# EEZ_DIB_BP3C_r2B3.net
KiCad netlist of a schematic drawn in EAGLE
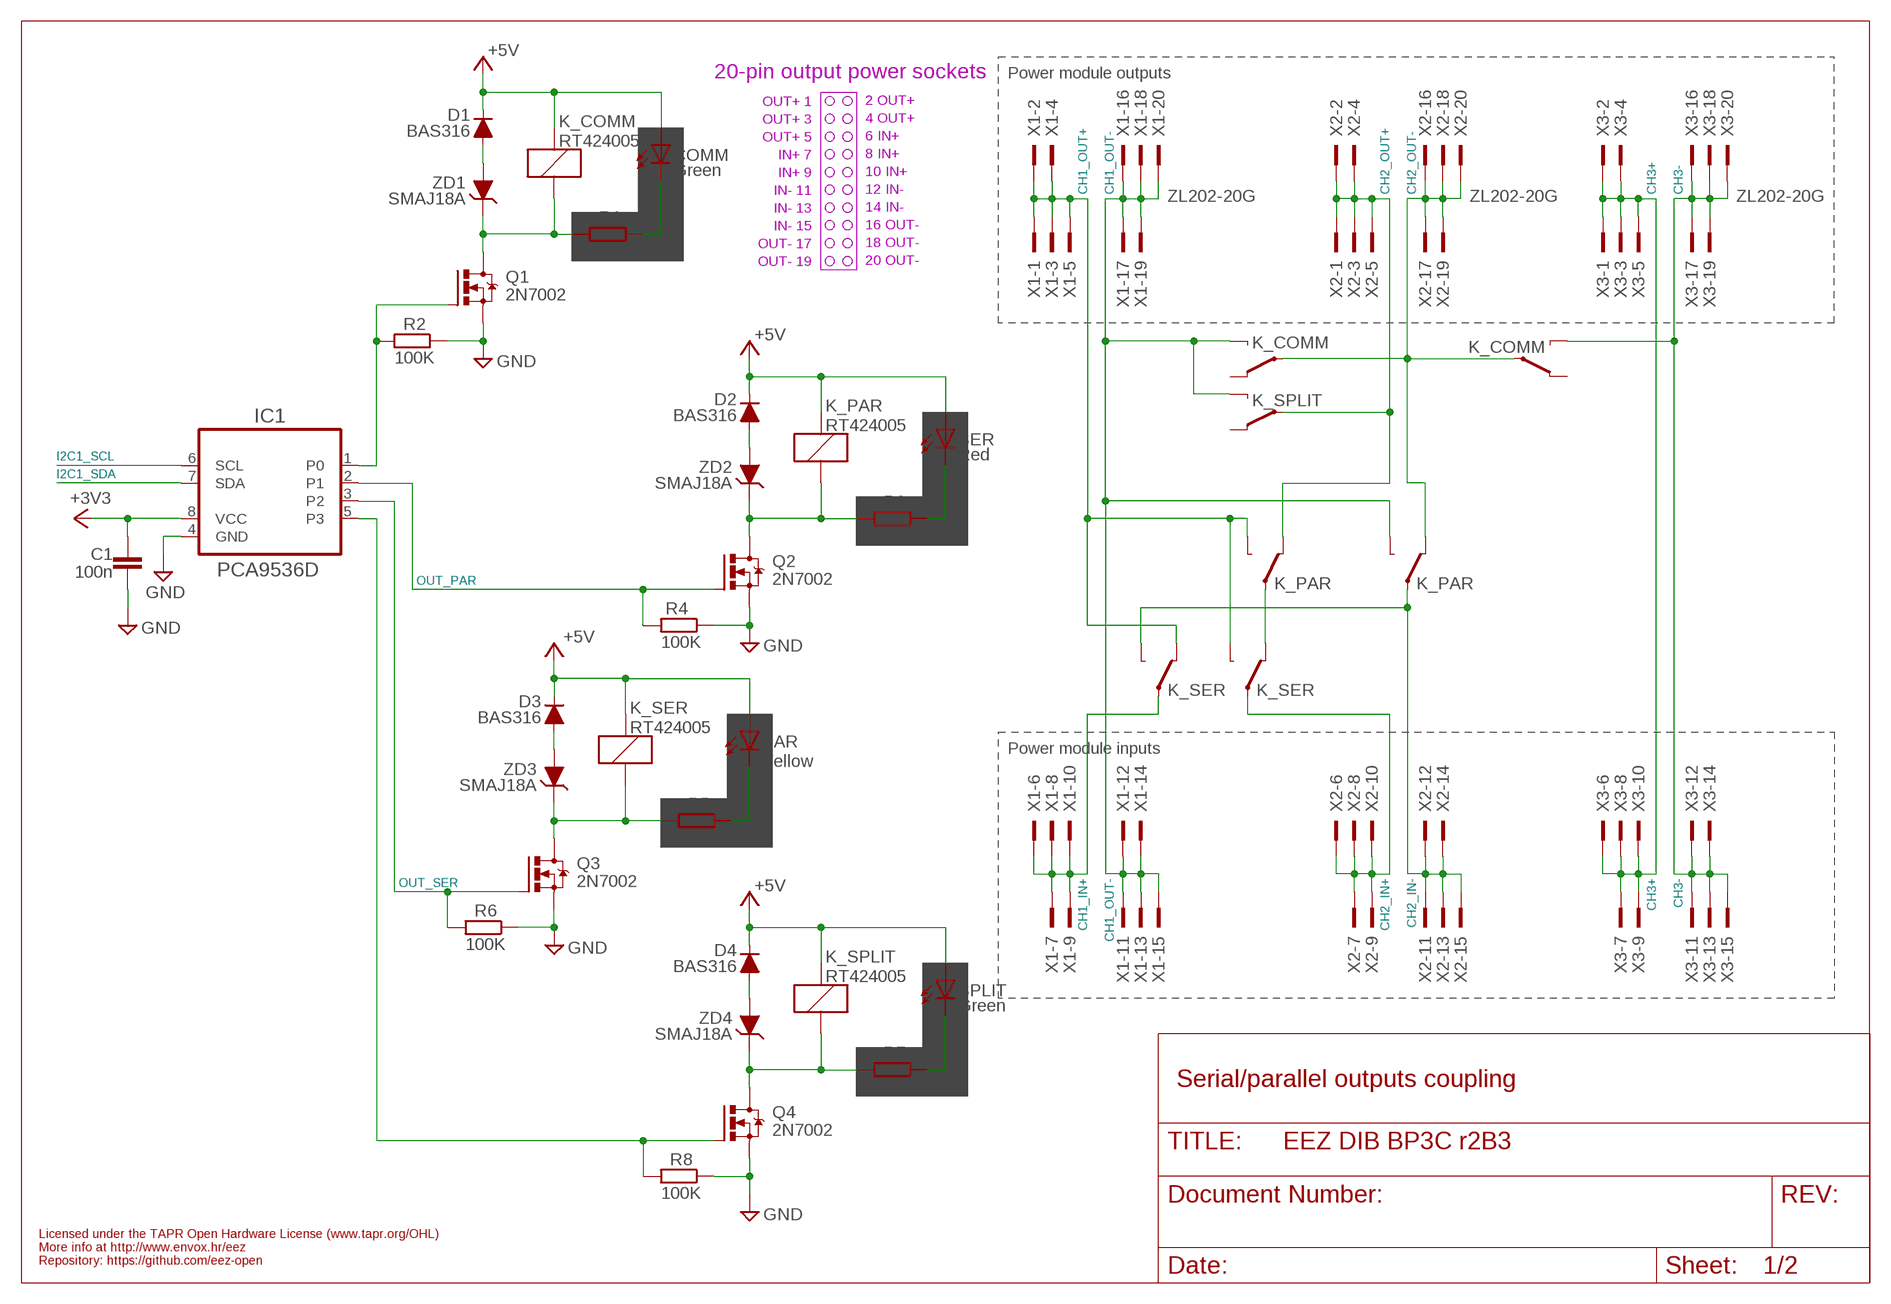
[diagram p0: schematic, sheet 1]
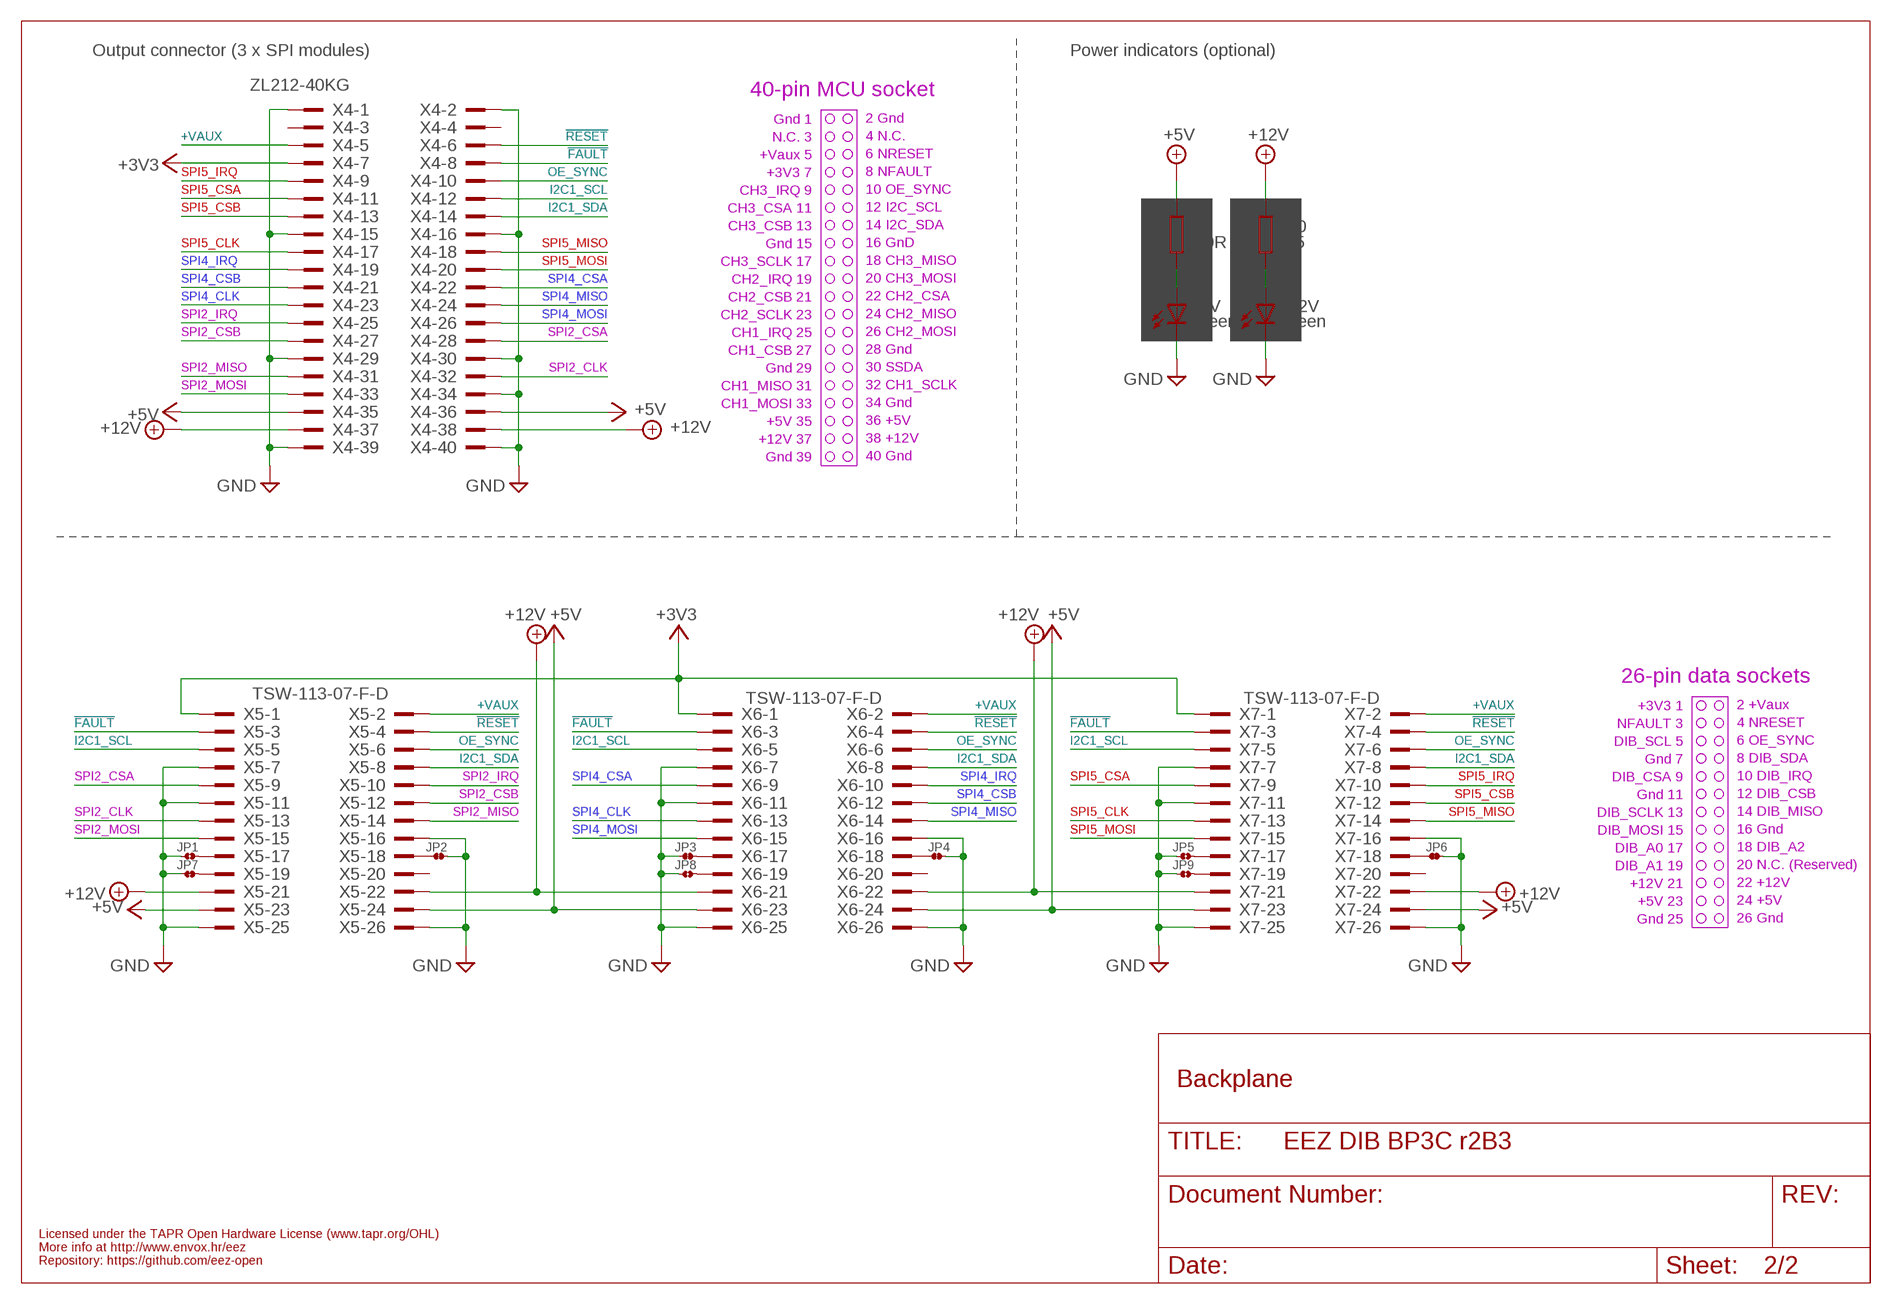
[diagram p1: schematic, sheet 2]

(export (version "E")
  (design (tool "Eeschema 10.0.6"))
  (components
    (comp (ref "+5V")
      (value "Green")
      (footprint "eagle-import:LED_0805")
      (libsource (lib "eagle-import") (part "LED0805"))
    )
    (comp (ref "+12V")
      (value "Green")
      (footprint "eagle-import:LED_0805")
      (libsource (lib "eagle-import") (part "LED0805"))
    )
    (comp (ref "JP1")
      (value "JP2-CUT")
      (footprint "eagle-import:JP2-CUT")
      (libsource (lib "eagle-import") (part "JP2-CUT"))
    )
    (comp (ref "JP2")
      (value "JP2-NOCUT")
      (footprint "eagle-import:JP2-NOCUT")
      (libsource (lib "eagle-import") (part "JP2-NOCUT"))
    )
    (comp (ref "JP3")
      (value "JP2-NOCUT")
      (footprint "eagle-import:JP2-NOCUT")
      (libsource (lib "eagle-import") (part "JP2-NOCUT"))
    )
    (comp (ref "JP4")
      (value "JP2-NOCUT")
      (footprint "eagle-import:JP2-NOCUT")
      (libsource (lib "eagle-import") (part "JP2-NOCUT"))
    )
    (comp (ref "JP5")
      (value "JP2-CUT")
      (footprint "eagle-import:JP2-CUT")
      (libsource (lib "eagle-import") (part "JP2-CUT"))
    )
    (comp (ref "JP6")
      (value "JP2-NOCUT")
      (footprint "eagle-import:JP2-NOCUT")
      (libsource (lib "eagle-import") (part "JP2-NOCUT"))
    )
    (comp (ref "JP7")
      (value "JP2-NOCUT")
      (footprint "eagle-import:JP2-NOCUT")
      (libsource (lib "eagle-import") (part "JP2-NOCUT"))
    )
    (comp (ref "JP8")
      (value "JP2-CUT")
      (footprint "eagle-import:JP2-CUT")
      (libsource (lib "eagle-import") (part "JP2-CUT"))
    )
    (comp (ref "JP9")
      (value "JP2-CUT")
      (footprint "eagle-import:JP2-CUT")
      (libsource (lib "eagle-import") (part "JP2-CUT"))
    )
    (comp (ref "R9")
      (value "470R")
      (footprint "eagle-import:R0805")
      (libsource (lib "eagle-import") (part "R-EU_R0805"))
    )
    (comp (ref "R10")
      (value "1K5")
      (footprint "eagle-import:R0805")
      (libsource (lib "eagle-import") (part "R-EU_R0805"))
    )
    (comp (ref "X4")
      (value "ZL212-40KG")
      (footprint "eagle-import:ZL212-40KG")
      (libsource (lib "eagle-import") (part "ZL212-40KG"))
    )
    (comp (ref "X5")
      (value "TSW-113-07-F-D")
      (footprint "eagle-import:TSW-113-07-F-D")
      (libsource (lib "eagle-import") (part "TSW-113-07-F-D"))
    )
    (comp (ref "X6")
      (value "TSW-113-07-F-D")
      (footprint "eagle-import:TSW-113-07-F-D")
      (libsource (lib "eagle-import") (part "TSW-113-07-F-D"))
    )
    (comp (ref "X7")
      (value "TSW-113-07-F-D")
      (footprint "eagle-import:TSW-113-07-F-D")
      (libsource (lib "eagle-import") (part "TSW-113-07-F-D"))
    )
    (comp (ref "C1")
      (value "100n")
      (footprint "eagle-import:C0603")
      (libsource (lib "eagle-import") (part "C-EUC0603"))
    )
    (comp (ref "COMM")
      (value "Green")
      (footprint "eagle-import:LED_0805")
      (libsource (lib "eagle-import") (part "LED0805"))
    )
    (comp (ref "D1")
      (value "BAS316")
      (footprint "eagle-import:SOD323-R")
      (libsource (lib "eagle-import") (part "DIODESOD323R"))
    )
    (comp (ref "D2")
      (value "BAS316")
      (footprint "eagle-import:SOD323-R")
      (libsource (lib "eagle-import") (part "DIODESOD323R"))
    )
    (comp (ref "D3")
      (value "BAS316")
      (footprint "eagle-import:SOD323-R")
      (libsource (lib "eagle-import") (part "DIODESOD323R"))
    )
    (comp (ref "D4")
      (value "BAS316")
      (footprint "eagle-import:SOD323-R")
      (libsource (lib "eagle-import") (part "DIODESOD323R"))
    )
    (comp (ref "IC1")
      (value "PCA9536D")
      (footprint "eagle-import:SOIC127P600X173-8N")
      (libsource (lib "eagle-import") (part "PCA9536D"))
    )
    (comp (ref "K_COMM")
      (value "RT424005")
      (footprint "eagle-import:RT-C_016A5_ROUND")
      (libsource (lib "eagle-import") (part "RELAY_RT314012-2"))
    )
    (comp (ref "K_PAR")
      (value "RT424005")
      (footprint "eagle-import:RT-C_016A5_ROUND")
      (libsource (lib "eagle-import") (part "RELAY_RT314012-2"))
    )
    (comp (ref "K_SER")
      (value "RT424005")
      (footprint "eagle-import:RT-C_016A5_ROUND")
      (libsource (lib "eagle-import") (part "RELAY_RT314012-2"))
    )
    (comp (ref "K_SPLIT")
      (value "RT424005")
      (footprint "eagle-import:RT-C_016A5_ROUND")
      (libsource (lib "eagle-import") (part "RELAY_RT314012-2"))
    )
    (comp (ref "PAR")
      (value "Yellow")
      (footprint "eagle-import:LED_0805")
      (libsource (lib "eagle-import") (part "LED0805"))
    )
    (comp (ref "Q1")
      (value "2N7002")
      (footprint "eagle-import:SOT103P240X110-3N")
      (fields
        (field (name "MPN") "2N7002-7-F")
        (field (name "MPN_1") "2N7002-7-F")
        (field (name "OC_FARNELL") "1713823")
        (field (name "OC_NEWARK") "25R5679")
        (field (name "PACKAGE") "SOT-23-3")
        (field (name "SUPPLIER") "DIODES INC.")
      )
      (libsource (lib "eagle-import") (part "2N7002"))
    )
    (comp (ref "Q2")
      (value "2N7002")
      (footprint "eagle-import:SOT103P240X110-3N")
      (fields
        (field (name "MPN") "2N7002-7-F")
        (field (name "MPN_1") "2N7002-7-F")
        (field (name "OC_FARNELL") "1713823")
        (field (name "OC_NEWARK") "25R5679")
        (field (name "PACKAGE") "SOT-23-3")
        (field (name "SUPPLIER") "DIODES INC.")
      )
      (libsource (lib "eagle-import") (part "2N7002"))
    )
    (comp (ref "Q3")
      (value "2N7002")
      (footprint "eagle-import:SOT103P240X110-3N")
      (fields
        (field (name "MPN") "2N7002-7-F")
        (field (name "MPN_1") "2N7002-7-F")
        (field (name "OC_FARNELL") "1713823")
        (field (name "OC_NEWARK") "25R5679")
        (field (name "PACKAGE") "SOT-23-3")
        (field (name "SUPPLIER") "DIODES INC.")
      )
      (libsource (lib "eagle-import") (part "2N7002"))
    )
    (comp (ref "Q4")
      (value "2N7002")
      (footprint "eagle-import:SOT103P240X110-3N")
      (fields
        (field (name "MPN") "2N7002-7-F")
        (field (name "MPN_1") "2N7002-7-F")
        (field (name "OC_FARNELL") "1713823")
        (field (name "OC_NEWARK") "25R5679")
        (field (name "PACKAGE") "SOT-23-3")
        (field (name "SUPPLIER") "DIODES INC.")
      )
      (libsource (lib "eagle-import") (part "2N7002"))
    )
    (comp (ref "R1")
      (value "330R")
      (footprint "eagle-import:R0805")
      (libsource (lib "eagle-import") (part "R-EU_R0805"))
    )
    (comp (ref "R2")
      (value "100K")
      (footprint "eagle-import:R0805")
      (libsource (lib "eagle-import") (part "R-EU_R0805"))
    )
    (comp (ref "R3")
      (value "330R")
      (footprint "eagle-import:R0805")
      (libsource (lib "eagle-import") (part "R-EU_R0805"))
    )
    (comp (ref "R4")
      (value "100K")
      (footprint "eagle-import:R0805")
      (libsource (lib "eagle-import") (part "R-EU_R0805"))
    )
    (comp (ref "R5")
      (value "330R")
      (footprint "eagle-import:R0805")
      (libsource (lib "eagle-import") (part "R-EU_R0805"))
    )
    (comp (ref "R6")
      (value "100K")
      (footprint "eagle-import:R0805")
      (libsource (lib "eagle-import") (part "R-EU_R0805"))
    )
    (comp (ref "R7")
      (value "330R")
      (footprint "eagle-import:R0805")
      (libsource (lib "eagle-import") (part "R-EU_R0805"))
    )
    (comp (ref "R8")
      (value "100K")
      (footprint "eagle-import:R0805")
      (libsource (lib "eagle-import") (part "R-EU_R0805"))
    )
    (comp (ref "SER")
      (value "Red")
      (footprint "eagle-import:LED_0805")
      (libsource (lib "eagle-import") (part "LED0805"))
    )
    (comp (ref "SPLIT")
      (value "Green")
      (footprint "eagle-import:LED_0805")
      (libsource (lib "eagle-import") (part "LED0805"))
    )
    (comp (ref "X1")
      (value "ZL202-20G")
      (footprint "eagle-import:DS1021-2_10SF11")
      (libsource (lib "eagle-import") (part "DS1021-210SF11"))
    )
    (comp (ref "X2")
      (value "ZL202-20G")
      (footprint "eagle-import:DS1021-2_10SF11")
      (libsource (lib "eagle-import") (part "DS1021-210SF11"))
    )
    (comp (ref "X3")
      (value "ZL202-20G")
      (footprint "eagle-import:DS1021-2_10SF11")
      (libsource (lib "eagle-import") (part "DS1021-210SF11"))
    )
    (comp (ref "ZD1")
      (value "SMAJ18A")
      (footprint "eagle-import:DO214AC")
      (libsource (lib "eagle-import") (part "PSMAXX"))
    )
    (comp (ref "ZD2")
      (value "SMAJ18A")
      (footprint "eagle-import:DO214AC")
      (libsource (lib "eagle-import") (part "PSMAXX"))
    )
    (comp (ref "ZD3")
      (value "SMAJ18A")
      (footprint "eagle-import:DO214AC")
      (libsource (lib "eagle-import") (part "PSMAXX"))
    )
    (comp (ref "ZD4")
      (value "SMAJ18A")
      (footprint "eagle-import:DO214AC")
      (libsource (lib "eagle-import") (part "PSMAXX"))
    )
  )
  (nets
    (net (code "1") (name "+3V3") (class "Default")
      (node (ref "C1") (pin "1") (pinfunction "1_1") (pintype "passive"))
      (node (ref "IC1") (pin "8") (pinfunction "VCC_8") (pintype "passive"))
      (node (ref "X4") (pin "7") (pinfunction "1_7") (pintype "passive"))
      (node (ref "X5") (pin "1") (pinfunction "1_1") (pintype "passive"))
      (node (ref "X6") (pin "1") (pinfunction "1_1") (pintype "passive"))
      (node (ref "X7") (pin "1") (pinfunction "1_1") (pintype "passive"))
    )
    (net (code "2") (name "+5V") (class "Default")
      (node (ref "COMM") (pin "A") (pinfunction "A_A") (pintype "passive"))
      (node (ref "D1") (pin "C") (pinfunction "C_C") (pintype "passive"))
      (node (ref "D2") (pin "C") (pinfunction "C_C") (pintype "passive"))
      (node (ref "D3") (pin "C") (pinfunction "C_C") (pintype "passive"))
      (node (ref "D4") (pin "C") (pinfunction "C_C") (pintype "passive"))
      (node (ref "K_COMM") (pin "A2") (pinfunction "C1_A2") (pintype "passive"))
      (node (ref "K_PAR") (pin "A2") (pinfunction "C1_A2") (pintype "passive"))
      (node (ref "K_SER") (pin "A2") (pinfunction "C1_A2") (pintype "passive"))
      (node (ref "K_SPLIT") (pin "A2") (pinfunction "C1_A2") (pintype "passive"))
      (node (ref "PAR") (pin "A") (pinfunction "A_A") (pintype "passive"))
      (node (ref "R9") (pin "1") (pinfunction "1_1") (pintype "passive"))
      (node (ref "SER") (pin "A") (pinfunction "A_A") (pintype "passive"))
      (node (ref "SPLIT") (pin "A") (pinfunction "A_A") (pintype "passive"))
      (node (ref "X4") (pin "35") (pinfunction "1_35") (pintype "passive"))
      (node (ref "X4") (pin "36") (pinfunction "1_36") (pintype "passive"))
      (node (ref "X5") (pin "23") (pinfunction "1_23") (pintype "passive"))
      (node (ref "X5") (pin "24") (pinfunction "1_24") (pintype "passive"))
      (node (ref "X6") (pin "23") (pinfunction "1_23") (pintype "passive"))
      (node (ref "X6") (pin "24") (pinfunction "1_24") (pintype "passive"))
      (node (ref "X7") (pin "23") (pinfunction "1_23") (pintype "passive"))
      (node (ref "X7") (pin "24") (pinfunction "1_24") (pintype "passive"))
    )
    (net (code "3") (name "+12V") (class "Default")
      (node (ref "R10") (pin "1") (pinfunction "1_1") (pintype "passive"))
      (node (ref "X4") (pin "37") (pinfunction "1_37") (pintype "passive"))
      (node (ref "X4") (pin "38") (pinfunction "1_38") (pintype "passive"))
      (node (ref "X5") (pin "21") (pinfunction "1_21") (pintype "passive"))
      (node (ref "X5") (pin "22") (pinfunction "1_22") (pintype "passive"))
      (node (ref "X6") (pin "21") (pinfunction "1_21") (pintype "passive"))
      (node (ref "X6") (pin "22") (pinfunction "1_22") (pintype "passive"))
      (node (ref "X7") (pin "21") (pinfunction "1_21") (pintype "passive"))
      (node (ref "X7") (pin "22") (pinfunction "1_22") (pintype "passive"))
    )
    (net (code "4") (name "+VAUX") (class "Default")
      (node (ref "X4") (pin "5") (pinfunction "1_5") (pintype "passive"))
      (node (ref "X5") (pin "2") (pinfunction "1_2") (pintype "passive"))
      (node (ref "X6") (pin "2") (pinfunction "1_2") (pintype "passive"))
      (node (ref "X7") (pin "2") (pinfunction "1_2") (pintype "passive"))
    )
    (net (code "5") (name "CH1_IN+") (class "Default")
      (node (ref "K_SER") (pin "11A") (pinfunction "P_11A") (pintype "passive"))
      (node (ref "X1") (pin "10") (pinfunction "1_10") (pintype "passive"))
      (node (ref "X1") (pin "6") (pinfunction "1_6") (pintype "passive"))
      (node (ref "X1") (pin "7") (pinfunction "1_7") (pintype "passive"))
      (node (ref "X1") (pin "8") (pinfunction "1_8") (pintype "passive"))
      (node (ref "X1") (pin "9") (pinfunction "1_9") (pintype "passive"))
    )
    (net (code "6") (name "CH1_OUT+") (class "Default")
      (node (ref "K_PAR") (pin "14A") (pinfunction "O_14A") (pintype "passive"))
      (node (ref "K_SER") (pin "12A") (pinfunction "S_12A") (pintype "passive"))
      (node (ref "K_SER") (pin "14B") (pinfunction "O_14B") (pintype "passive"))
      (node (ref "X1") (pin "1") (pinfunction "1_1") (pintype "passive"))
      (node (ref "X1") (pin "2") (pinfunction "1_2") (pintype "passive"))
      (node (ref "X1") (pin "3") (pinfunction "1_3") (pintype "passive"))
      (node (ref "X1") (pin "4") (pinfunction "1_4") (pintype "passive"))
      (node (ref "X1") (pin "5") (pinfunction "1_5") (pintype "passive"))
    )
    (net (code "7") (name "CH1_OUT-") (class "Default")
      (node (ref "K_COMM") (pin "14A") (pinfunction "O_14A") (pintype "passive"))
      (node (ref "K_PAR") (pin "14B") (pinfunction "O_14B") (pintype "passive"))
      (node (ref "K_SPLIT") (pin "14A") (pinfunction "O_14A") (pintype "passive"))
      (node (ref "X1") (pin "11") (pinfunction "1_11") (pintype "passive"))
      (node (ref "X1") (pin "12") (pinfunction "1_12") (pintype "passive"))
      (node (ref "X1") (pin "13") (pinfunction "1_13") (pintype "passive"))
      (node (ref "X1") (pin "14") (pinfunction "1_14") (pintype "passive"))
      (node (ref "X1") (pin "15") (pinfunction "1_15") (pintype "passive"))
      (node (ref "X1") (pin "16") (pinfunction "1_16") (pintype "passive"))
      (node (ref "X1") (pin "17") (pinfunction "1_17") (pintype "passive"))
      (node (ref "X1") (pin "18") (pinfunction "1_18") (pintype "passive"))
      (node (ref "X1") (pin "19") (pinfunction "1_19") (pintype "passive"))
      (node (ref "X1") (pin "20") (pinfunction "1_20") (pintype "passive"))
    )
    (net (code "8") (name "CH2_IN+") (class "Default")
      (node (ref "K_SER") (pin "11B") (pinfunction "P_11B") (pintype "passive"))
      (node (ref "X2") (pin "10") (pinfunction "1_10") (pintype "passive"))
      (node (ref "X2") (pin "6") (pinfunction "1_6") (pintype "passive"))
      (node (ref "X2") (pin "7") (pinfunction "1_7") (pintype "passive"))
      (node (ref "X2") (pin "8") (pinfunction "1_8") (pintype "passive"))
      (node (ref "X2") (pin "9") (pinfunction "1_9") (pintype "passive"))
    )
    (net (code "9") (name "CH2_IN-") (class "Default")
      (node (ref "K_PAR") (pin "11B") (pinfunction "P_11B") (pintype "passive"))
      (node (ref "K_SER") (pin "14A") (pinfunction "O_14A") (pintype "passive"))
      (node (ref "X2") (pin "11") (pinfunction "1_11") (pintype "passive"))
      (node (ref "X2") (pin "12") (pinfunction "1_12") (pintype "passive"))
      (node (ref "X2") (pin "13") (pinfunction "1_13") (pintype "passive"))
      (node (ref "X2") (pin "14") (pinfunction "1_14") (pintype "passive"))
      (node (ref "X2") (pin "15") (pinfunction "1_15") (pintype "passive"))
    )
    (net (code "10") (name "CH2_OUT+") (class "Default")
      (node (ref "K_PAR") (pin "12A") (pinfunction "S_12A") (pintype "passive"))
      (node (ref "K_SPLIT") (pin "11A") (pinfunction "P_11A") (pintype "passive"))
      (node (ref "X2") (pin "1") (pinfunction "1_1") (pintype "passive"))
      (node (ref "X2") (pin "2") (pinfunction "1_2") (pintype "passive"))
      (node (ref "X2") (pin "3") (pinfunction "1_3") (pintype "passive"))
      (node (ref "X2") (pin "4") (pinfunction "1_4") (pintype "passive"))
      (node (ref "X2") (pin "5") (pinfunction "1_5") (pintype "passive"))
    )
    (net (code "11") (name "CH2_OUT-") (class "Default")
      (node (ref "K_COMM") (pin "11A") (pinfunction "P_11A") (pintype "passive"))
      (node (ref "K_COMM") (pin "11B") (pinfunction "P_11B") (pintype "passive"))
      (node (ref "K_PAR") (pin "12B") (pinfunction "S_12B") (pintype "passive"))
      (node (ref "X2") (pin "16") (pinfunction "1_16") (pintype "passive"))
      (node (ref "X2") (pin "17") (pinfunction "1_17") (pintype "passive"))
      (node (ref "X2") (pin "18") (pinfunction "1_18") (pintype "passive"))
      (node (ref "X2") (pin "19") (pinfunction "1_19") (pintype "passive"))
      (node (ref "X2") (pin "20") (pinfunction "1_20") (pintype "passive"))
    )
    (net (code "12") (name "CH3+") (class "Default")
      (node (ref "X3") (pin "1") (pinfunction "1_1") (pintype "passive"))
      (node (ref "X3") (pin "10") (pinfunction "1_10") (pintype "passive"))
      (node (ref "X3") (pin "2") (pinfunction "1_2") (pintype "passive"))
      (node (ref "X3") (pin "3") (pinfunction "1_3") (pintype "passive"))
      (node (ref "X3") (pin "4") (pinfunction "1_4") (pintype "passive"))
      (node (ref "X3") (pin "5") (pinfunction "1_5") (pintype "passive"))
      (node (ref "X3") (pin "6") (pinfunction "1_6") (pintype "passive"))
      (node (ref "X3") (pin "7") (pinfunction "1_7") (pintype "passive"))
      (node (ref "X3") (pin "8") (pinfunction "1_8") (pintype "passive"))
      (node (ref "X3") (pin "9") (pinfunction "1_9") (pintype "passive"))
    )
    (net (code "13") (name "CH3-") (class "Default")
      (node (ref "K_COMM") (pin "14B") (pinfunction "O_14B") (pintype "passive"))
      (node (ref "X3") (pin "11") (pinfunction "1_11") (pintype "passive"))
      (node (ref "X3") (pin "12") (pinfunction "1_12") (pintype "passive"))
      (node (ref "X3") (pin "13") (pinfunction "1_13") (pintype "passive"))
      (node (ref "X3") (pin "14") (pinfunction "1_14") (pintype "passive"))
      (node (ref "X3") (pin "15") (pinfunction "1_15") (pintype "passive"))
      (node (ref "X3") (pin "16") (pinfunction "1_16") (pintype "passive"))
      (node (ref "X3") (pin "17") (pinfunction "1_17") (pintype "passive"))
      (node (ref "X3") (pin "18") (pinfunction "1_18") (pintype "passive"))
      (node (ref "X3") (pin "19") (pinfunction "1_19") (pintype "passive"))
      (node (ref "X3") (pin "20") (pinfunction "1_20") (pintype "passive"))
    )
    (net (code "14") (name "GND") (class "Default")
      (node (ref "+12V") (pin "C") (pinfunction "C_C") (pintype "passive"))
      (node (ref "+5V") (pin "C") (pinfunction "C_C") (pintype "passive"))
      (node (ref "C1") (pin "2") (pinfunction "2_2") (pintype "passive"))
      (node (ref "IC1") (pin "4") (pinfunction "GND_4") (pintype "passive"))
      (node (ref "JP1") (pin "1") (pinfunction "1_1") (pintype "passive"))
      (node (ref "JP2") (pin "2") (pinfunction "2_2") (pintype "passive"))
      (node (ref "JP3") (pin "1") (pinfunction "1_1") (pintype "passive"))
      (node (ref "JP4") (pin "2") (pinfunction "2_2") (pintype "passive"))
      (node (ref "JP5") (pin "1") (pinfunction "1_1") (pintype "passive"))
      (node (ref "JP6") (pin "2") (pinfunction "2_2") (pintype "passive"))
      (node (ref "JP7") (pin "1") (pinfunction "1_1") (pintype "passive"))
      (node (ref "JP8") (pin "1") (pinfunction "1_1") (pintype "passive"))
      (node (ref "JP9") (pin "1") (pinfunction "1_1") (pintype "passive"))
      (node (ref "Q1") (pin "2") (pinfunction "S_2") (pintype "passive"))
      (node (ref "Q2") (pin "2") (pinfunction "S_2") (pintype "passive"))
      (node (ref "Q3") (pin "2") (pinfunction "S_2") (pintype "passive"))
      (node (ref "Q4") (pin "2") (pinfunction "S_2") (pintype "passive"))
      (node (ref "R2") (pin "1") (pinfunction "1_1") (pintype "passive"))
      (node (ref "R4") (pin "1") (pinfunction "1_1") (pintype "passive"))
      (node (ref "R6") (pin "1") (pinfunction "1_1") (pintype "passive"))
      (node (ref "R8") (pin "1") (pinfunction "1_1") (pintype "passive"))
      (node (ref "X4") (pin "1") (pinfunction "1_1") (pintype "passive"))
      (node (ref "X4") (pin "15") (pinfunction "1_15") (pintype "passive"))
      (node (ref "X4") (pin "16") (pinfunction "1_16") (pintype "passive"))
      (node (ref "X4") (pin "2") (pinfunction "1_2") (pintype "passive"))
      (node (ref "X4") (pin "29") (pinfunction "1_29") (pintype "passive"))
      (node (ref "X4") (pin "30") (pinfunction "1_30") (pintype "passive"))
      (node (ref "X4") (pin "34") (pinfunction "1_34") (pintype "passive"))
      (node (ref "X4") (pin "39") (pinfunction "1_39") (pintype "passive"))
      (node (ref "X4") (pin "40") (pinfunction "1_40") (pintype "passive"))
      (node (ref "X5") (pin "11") (pinfunction "1_11") (pintype "passive"))
      (node (ref "X5") (pin "16") (pinfunction "1_16") (pintype "passive"))
      (node (ref "X5") (pin "25") (pinfunction "1_25") (pintype "passive"))
      (node (ref "X5") (pin "26") (pinfunction "1_26") (pintype "passive"))
      (node (ref "X5") (pin "7") (pinfunction "1_7") (pintype "passive"))
      (node (ref "X6") (pin "11") (pinfunction "1_11") (pintype "passive"))
      (node (ref "X6") (pin "16") (pinfunction "1_16") (pintype "passive"))
      (node (ref "X6") (pin "25") (pinfunction "1_25") (pintype "passive"))
      (node (ref "X6") (pin "26") (pinfunction "1_26") (pintype "passive"))
      (node (ref "X6") (pin "7") (pinfunction "1_7") (pintype "passive"))
      (node (ref "X7") (pin "11") (pinfunction "1_11") (pintype "passive"))
      (node (ref "X7") (pin "16") (pinfunction "1_16") (pintype "passive"))
      (node (ref "X7") (pin "25") (pinfunction "1_25") (pintype "passive"))
      (node (ref "X7") (pin "26") (pinfunction "1_26") (pintype "passive"))
      (node (ref "X7") (pin "7") (pinfunction "1_7") (pintype "passive"))
    )
    (net (code "15") (name "I2C1_SCL") (class "Default")
      (node (ref "IC1") (pin "6") (pinfunction "SCL_6") (pintype "input"))
      (node (ref "X4") (pin "12") (pinfunction "1_12") (pintype "passive"))
      (node (ref "X5") (pin "5") (pinfunction "1_5") (pintype "passive"))
      (node (ref "X6") (pin "5") (pinfunction "1_5") (pintype "passive"))
      (node (ref "X7") (pin "5") (pinfunction "1_5") (pintype "passive"))
    )
    (net (code "16") (name "I2C1_SDA") (class "Default")
      (node (ref "IC1") (pin "7") (pinfunction "SDA_7") (pintype "bidirectional"))
      (node (ref "X4") (pin "14") (pinfunction "1_14") (pintype "passive"))
      (node (ref "X5") (pin "8") (pinfunction "1_8") (pintype "passive"))
      (node (ref "X6") (pin "8") (pinfunction "1_8") (pintype "passive"))
      (node (ref "X7") (pin "8") (pinfunction "1_8") (pintype "passive"))
    )
    (net (code "17") (name "Net-(+5V-PadA)") (class "Default")
      (node (ref "+5V") (pin "A") (pinfunction "A_A") (pintype "passive"))
      (node (ref "R9") (pin "2") (pinfunction "2_2") (pintype "passive"))
    )
    (net (code "18") (name "Net-(+12V-PadA)") (class "Default")
      (node (ref "+12V") (pin "A") (pinfunction "A_A") (pintype "passive"))
      (node (ref "R10") (pin "2") (pinfunction "2_2") (pintype "passive"))
    )
    (net (code "19") (name "Net-(COMM-PadC)") (class "Default")
      (node (ref "COMM") (pin "C") (pinfunction "C_C") (pintype "passive"))
      (node (ref "R1") (pin "1") (pinfunction "1_1") (pintype "passive"))
    )
    (net (code "20") (name "Net-(D1-PadA)") (class "Default")
      (node (ref "D1") (pin "A") (pinfunction "A_A") (pintype "passive"))
      (node (ref "ZD1") (pin "A") (pinfunction "A_A") (pintype "passive"))
    )
    (net (code "21") (name "Net-(D2-PadA)") (class "Default")
      (node (ref "D2") (pin "A") (pinfunction "A_A") (pintype "passive"))
      (node (ref "ZD2") (pin "A") (pinfunction "A_A") (pintype "passive"))
    )
    (net (code "22") (name "Net-(D3-PadA)") (class "Default")
      (node (ref "D3") (pin "A") (pinfunction "A_A") (pintype "passive"))
      (node (ref "ZD3") (pin "A") (pinfunction "A_A") (pintype "passive"))
    )
    (net (code "23") (name "Net-(D4-PadA)") (class "Default")
      (node (ref "D4") (pin "A") (pinfunction "A_A") (pintype "passive"))
      (node (ref "ZD4") (pin "A") (pinfunction "A_A") (pintype "passive"))
    )
    (net (code "24") (name "Net-(IC1-P0)") (class "Default")
      (node (ref "IC1") (pin "1") (pinfunction "P0_1") (pintype "bidirectional"))
      (node (ref "Q1") (pin "1") (pinfunction "G_1") (pintype "passive"))
      (node (ref "R2") (pin "2") (pinfunction "2_2") (pintype "passive"))
    )
    (net (code "25") (name "Net-(IC1-P3)") (class "Default")
      (node (ref "IC1") (pin "5") (pinfunction "P3_5") (pintype "bidirectional"))
      (node (ref "Q4") (pin "1") (pinfunction "G_1") (pintype "passive"))
      (node (ref "R8") (pin "2") (pinfunction "2_2") (pintype "passive"))
    )
    (net (code "26") (name "Net-(K_COMMC-C2)") (class "Default")
      (node (ref "K_COMM") (pin "A1") (pinfunction "C2_A1") (pintype "passive"))
      (node (ref "Q1") (pin "3") (pinfunction "D_3") (pintype "passive"))
      (node (ref "R1") (pin "2") (pinfunction "2_2") (pintype "passive"))
      (node (ref "ZD1") (pin "C") (pinfunction "C_C") (pintype "passive"))
    )
    (net (code "27") (name "Net-(K_PARA-P)") (class "Default")
      (node (ref "K_PAR") (pin "11A") (pinfunction "P_11A") (pintype "passive"))
      (node (ref "K_SER") (pin "12B") (pinfunction "S_12B") (pintype "passive"))
    )
    (net (code "28") (name "Net-(K_PARC-C2)") (class "Default")
      (node (ref "K_PAR") (pin "A1") (pinfunction "C2_A1") (pintype "passive"))
      (node (ref "Q2") (pin "3") (pinfunction "D_3") (pintype "passive"))
      (node (ref "R3") (pin "2") (pinfunction "2_2") (pintype "passive"))
      (node (ref "ZD2") (pin "C") (pinfunction "C_C") (pintype "passive"))
    )
    (net (code "29") (name "Net-(K_SERC-C2)") (class "Default")
      (node (ref "K_SER") (pin "A1") (pinfunction "C2_A1") (pintype "passive"))
      (node (ref "Q3") (pin "3") (pinfunction "D_3") (pintype "passive"))
      (node (ref "R5") (pin "2") (pinfunction "2_2") (pintype "passive"))
      (node (ref "ZD3") (pin "C") (pinfunction "C_C") (pintype "passive"))
    )
    (net (code "30") (name "Net-(K_SPLITC-C2)") (class "Default")
      (node (ref "K_SPLIT") (pin "A1") (pinfunction "C2_A1") (pintype "passive"))
      (node (ref "Q4") (pin "3") (pinfunction "D_3") (pintype "passive"))
      (node (ref "R7") (pin "2") (pinfunction "2_2") (pintype "passive"))
      (node (ref "ZD4") (pin "C") (pinfunction "C_C") (pintype "passive"))
    )
    (net (code "31") (name "Net-(PAR-PadC)") (class "Default")
      (node (ref "PAR") (pin "C") (pinfunction "C_C") (pintype "passive"))
      (node (ref "R5") (pin "1") (pinfunction "1_1") (pintype "passive"))
    )
    (net (code "32") (name "Net-(R3-Pad1)") (class "Default")
      (node (ref "R3") (pin "1") (pinfunction "1_1") (pintype "passive"))
      (node (ref "SER") (pin "C") (pinfunction "C_C") (pintype "passive"))
    )
    (net (code "33") (name "Net-(R7-Pad1)") (class "Default")
      (node (ref "R7") (pin "1") (pinfunction "1_1") (pintype "passive"))
      (node (ref "SPLIT") (pin "C") (pinfunction "C_C") (pintype "passive"))
    )
    (net (code "34") (name "Net-(X5I-1)") (class "Default")
      (node (ref "JP1") (pin "2") (pinfunction "2_2") (pintype "passive"))
      (node (ref "X5") (pin "17") (pinfunction "1_17") (pintype "passive"))
    )
    (net (code "35") (name "Net-(X5J-1)") (class "Default")
      (node (ref "JP2") (pin "1") (pinfunction "1_1") (pintype "passive"))
      (node (ref "X5") (pin "18") (pinfunction "1_18") (pintype "passive"))
    )
    (net (code "36") (name "Net-(X5K-1)") (class "Default")
      (node (ref "JP7") (pin "2") (pinfunction "2_2") (pintype "passive"))
      (node (ref "X5") (pin "19") (pinfunction "1_19") (pintype "passive"))
    )
    (net (code "37") (name "Net-(X6I-1)") (class "Default")
      (node (ref "JP3") (pin "2") (pinfunction "2_2") (pintype "passive"))
      (node (ref "X6") (pin "17") (pinfunction "1_17") (pintype "passive"))
    )
    (net (code "38") (name "Net-(X6J-1)") (class "Default")
      (node (ref "JP4") (pin "1") (pinfunction "1_1") (pintype "passive"))
      (node (ref "X6") (pin "18") (pinfunction "1_18") (pintype "passive"))
    )
    (net (code "39") (name "Net-(X6K-1)") (class "Default")
      (node (ref "JP8") (pin "2") (pinfunction "2_2") (pintype "passive"))
      (node (ref "X6") (pin "19") (pinfunction "1_19") (pintype "passive"))
    )
    (net (code "40") (name "Net-(X7I-1)") (class "Default")
      (node (ref "JP5") (pin "2") (pinfunction "2_2") (pintype "passive"))
      (node (ref "X7") (pin "17") (pinfunction "1_17") (pintype "passive"))
    )
    (net (code "41") (name "Net-(X7J-1)") (class "Default")
      (node (ref "JP6") (pin "1") (pinfunction "1_1") (pintype "passive"))
      (node (ref "X7") (pin "18") (pinfunction "1_18") (pintype "passive"))
    )
    (net (code "42") (name "Net-(X7K-1)") (class "Default")
      (node (ref "JP9") (pin "2") (pinfunction "2_2") (pintype "passive"))
      (node (ref "X7") (pin "19") (pinfunction "1_19") (pintype "passive"))
    )
    (net (code "43") (name "OE_SYNC") (class "Default")
      (node (ref "X4") (pin "10") (pinfunction "1_10") (pintype "passive"))
      (node (ref "X5") (pin "6") (pinfunction "1_6") (pintype "passive"))
      (node (ref "X6") (pin "6") (pinfunction "1_6") (pintype "passive"))
      (node (ref "X7") (pin "6") (pinfunction "1_6") (pintype "passive"))
    )
    (net (code "44") (name "OUT_PAR") (class "Default")
      (node (ref "IC1") (pin "2") (pinfunction "P1_2") (pintype "bidirectional"))
      (node (ref "Q2") (pin "1") (pinfunction "G_1") (pintype "passive"))
      (node (ref "R4") (pin "2") (pinfunction "2_2") (pintype "passive"))
    )
    (net (code "45") (name "OUT_SER") (class "Default")
      (node (ref "IC1") (pin "3") (pinfunction "P2_3") (pintype "bidirectional"))
      (node (ref "Q3") (pin "1") (pinfunction "G_1") (pintype "passive"))
      (node (ref "R6") (pin "2") (pinfunction "2_2") (pintype "passive"))
    )
    (net (code "46") (name "SPI2_CLK") (class "Default")
      (node (ref "X4") (pin "32") (pinfunction "1_32") (pintype "passive"))
      (node (ref "X5") (pin "13") (pinfunction "1_13") (pintype "passive"))
    )
    (net (code "47") (name "SPI2_CSA") (class "Default")
      (node (ref "X4") (pin "28") (pinfunction "1_28") (pintype "passive"))
      (node (ref "X5") (pin "9") (pinfunction "1_9") (pintype "passive"))
    )
    (net (code "48") (name "SPI2_CSB") (class "Default")
      (node (ref "X4") (pin "27") (pinfunction "1_27") (pintype "passive"))
      (node (ref "X5") (pin "12") (pinfunction "1_12") (pintype "passive"))
    )
    (net (code "49") (name "SPI2_IRQ") (class "Default")
      (node (ref "X4") (pin "25") (pinfunction "1_25") (pintype "passive"))
      (node (ref "X5") (pin "10") (pinfunction "1_10") (pintype "passive"))
    )
    (net (code "50") (name "SPI2_MISO") (class "Default")
      (node (ref "X4") (pin "31") (pinfunction "1_31") (pintype "passive"))
      (node (ref "X5") (pin "14") (pinfunction "1_14") (pintype "passive"))
    )
    (net (code "51") (name "SPI2_MOSI") (class "Default")
      (node (ref "X4") (pin "33") (pinfunction "1_33") (pintype "passive"))
      (node (ref "X5") (pin "15") (pinfunction "1_15") (pintype "passive"))
    )
    (net (code "52") (name "SPI4_CLK") (class "Default")
      (node (ref "X4") (pin "23") (pinfunction "1_23") (pintype "passive"))
      (node (ref "X6") (pin "13") (pinfunction "1_13") (pintype "passive"))
    )
    (net (code "53") (name "SPI4_CSA") (class "Default")
      (node (ref "X4") (pin "22") (pinfunction "1_22") (pintype "passive"))
      (node (ref "X6") (pin "9") (pinfunction "1_9") (pintype "passive"))
    )
    (net (code "54") (name "SPI4_CSB") (class "Default")
      (node (ref "X4") (pin "21") (pinfunction "1_21") (pintype "passive"))
      (node (ref "X6") (pin "12") (pinfunction "1_12") (pintype "passive"))
    )
    (net (code "55") (name "SPI4_IRQ") (class "Default")
      (node (ref "X4") (pin "19") (pinfunction "1_19") (pintype "passive"))
      (node (ref "X6") (pin "10") (pinfunction "1_10") (pintype "passive"))
    )
    (net (code "56") (name "SPI4_MISO") (class "Default")
      (node (ref "X4") (pin "24") (pinfunction "1_24") (pintype "passive"))
      (node (ref "X6") (pin "14") (pinfunction "1_14") (pintype "passive"))
    )
    (net (code "57") (name "SPI4_MOSI") (class "Default")
      (node (ref "X4") (pin "26") (pinfunction "1_26") (pintype "passive"))
      (node (ref "X6") (pin "15") (pinfunction "1_15") (pintype "passive"))
    )
    (net (code "58") (name "SPI5_CLK") (class "Default")
      (node (ref "X4") (pin "17") (pinfunction "1_17") (pintype "passive"))
      (node (ref "X7") (pin "13") (pinfunction "1_13") (pintype "passive"))
    )
    (net (code "59") (name "SPI5_CSA") (class "Default")
      (node (ref "X4") (pin "11") (pinfunction "1_11") (pintype "passive"))
      (node (ref "X7") (pin "9") (pinfunction "1_9") (pintype "passive"))
    )
    (net (code "60") (name "SPI5_CSB") (class "Default")
      (node (ref "X4") (pin "13") (pinfunction "1_13") (pintype "passive"))
      (node (ref "X7") (pin "12") (pinfunction "1_12") (pintype "passive"))
    )
    (net (code "61") (name "SPI5_IRQ") (class "Default")
      (node (ref "X4") (pin "9") (pinfunction "1_9") (pintype "passive"))
      (node (ref "X7") (pin "10") (pinfunction "1_10") (pintype "passive"))
    )
    (net (code "62") (name "SPI5_MISO") (class "Default")
      (node (ref "X4") (pin "18") (pinfunction "1_18") (pintype "passive"))
      (node (ref "X7") (pin "14") (pinfunction "1_14") (pintype "passive"))
    )
    (net (code "63") (name "SPI5_MOSI") (class "Default")
      (node (ref "X4") (pin "20") (pinfunction "1_20") (pintype "passive"))
      (node (ref "X7") (pin "15") (pinfunction "1_15") (pintype "passive"))
    )
    (net (code "64") (name "unconnected-(K_COMMA-S-Pad12A)") (class "Default")
      (node (ref "K_COMM") (pin "12A") (pinfunction "S_12A") (pintype "passive"))
    )
    (net (code "65") (name "unconnected-(K_COMMB-S-Pad12B)") (class "Default")
      (node (ref "K_COMM") (pin "12B") (pinfunction "S_12B") (pintype "passive"))
    )
    (net (code "66") (name "unconnected-(K_SPLITA-S-Pad12A)") (class "Default")
      (node (ref "K_SPLIT") (pin "12A") (pinfunction "S_12A") (pintype "passive"))
    )
    (net (code "67") (name "unconnected-(X4AH-1-Pad4)") (class "Default")
      (node (ref "X4") (pin "4") (pinfunction "1_4") (pintype "passive"))
    )
    (net (code "68") (name "unconnected-(X4W-1-Pad3)") (class "Default")
      (node (ref "X4") (pin "3") (pinfunction "1_3") (pintype "passive"))
    )
    (net (code "69") (name "unconnected-(X5M-1-Pad20)") (class "Default")
      (node (ref "X5") (pin "20") (pinfunction "1_20") (pintype "passive"))
    )
    (net (code "70") (name "unconnected-(X6M-1-Pad20)") (class "Default")
      (node (ref "X6") (pin "20") (pinfunction "1_20") (pintype "passive"))
    )
    (net (code "71") (name "unconnected-(X7M-1-Pad20)") (class "Default")
      (node (ref "X7") (pin "20") (pinfunction "1_20") (pintype "passive"))
    )
    (net (code "72") (name "~{FAULT}") (class "Default")
      (node (ref "X4") (pin "8") (pinfunction "1_8") (pintype "passive"))
      (node (ref "X5") (pin "3") (pinfunction "1_3") (pintype "passive"))
      (node (ref "X6") (pin "3") (pinfunction "1_3") (pintype "passive"))
      (node (ref "X7") (pin "3") (pinfunction "1_3") (pintype "passive"))
    )
    (net (code "73") (name "~{RESET}") (class "Default")
      (node (ref "X4") (pin "6") (pinfunction "1_6") (pintype "passive"))
      (node (ref "X5") (pin "4") (pinfunction "1_4") (pintype "passive"))
      (node (ref "X6") (pin "4") (pinfunction "1_4") (pintype "passive"))
      (node (ref "X7") (pin "4") (pinfunction "1_4") (pintype "passive"))
    )
  )
)
